# Main1.net
KiCad netlist of a schematic drawn in Altium Designer
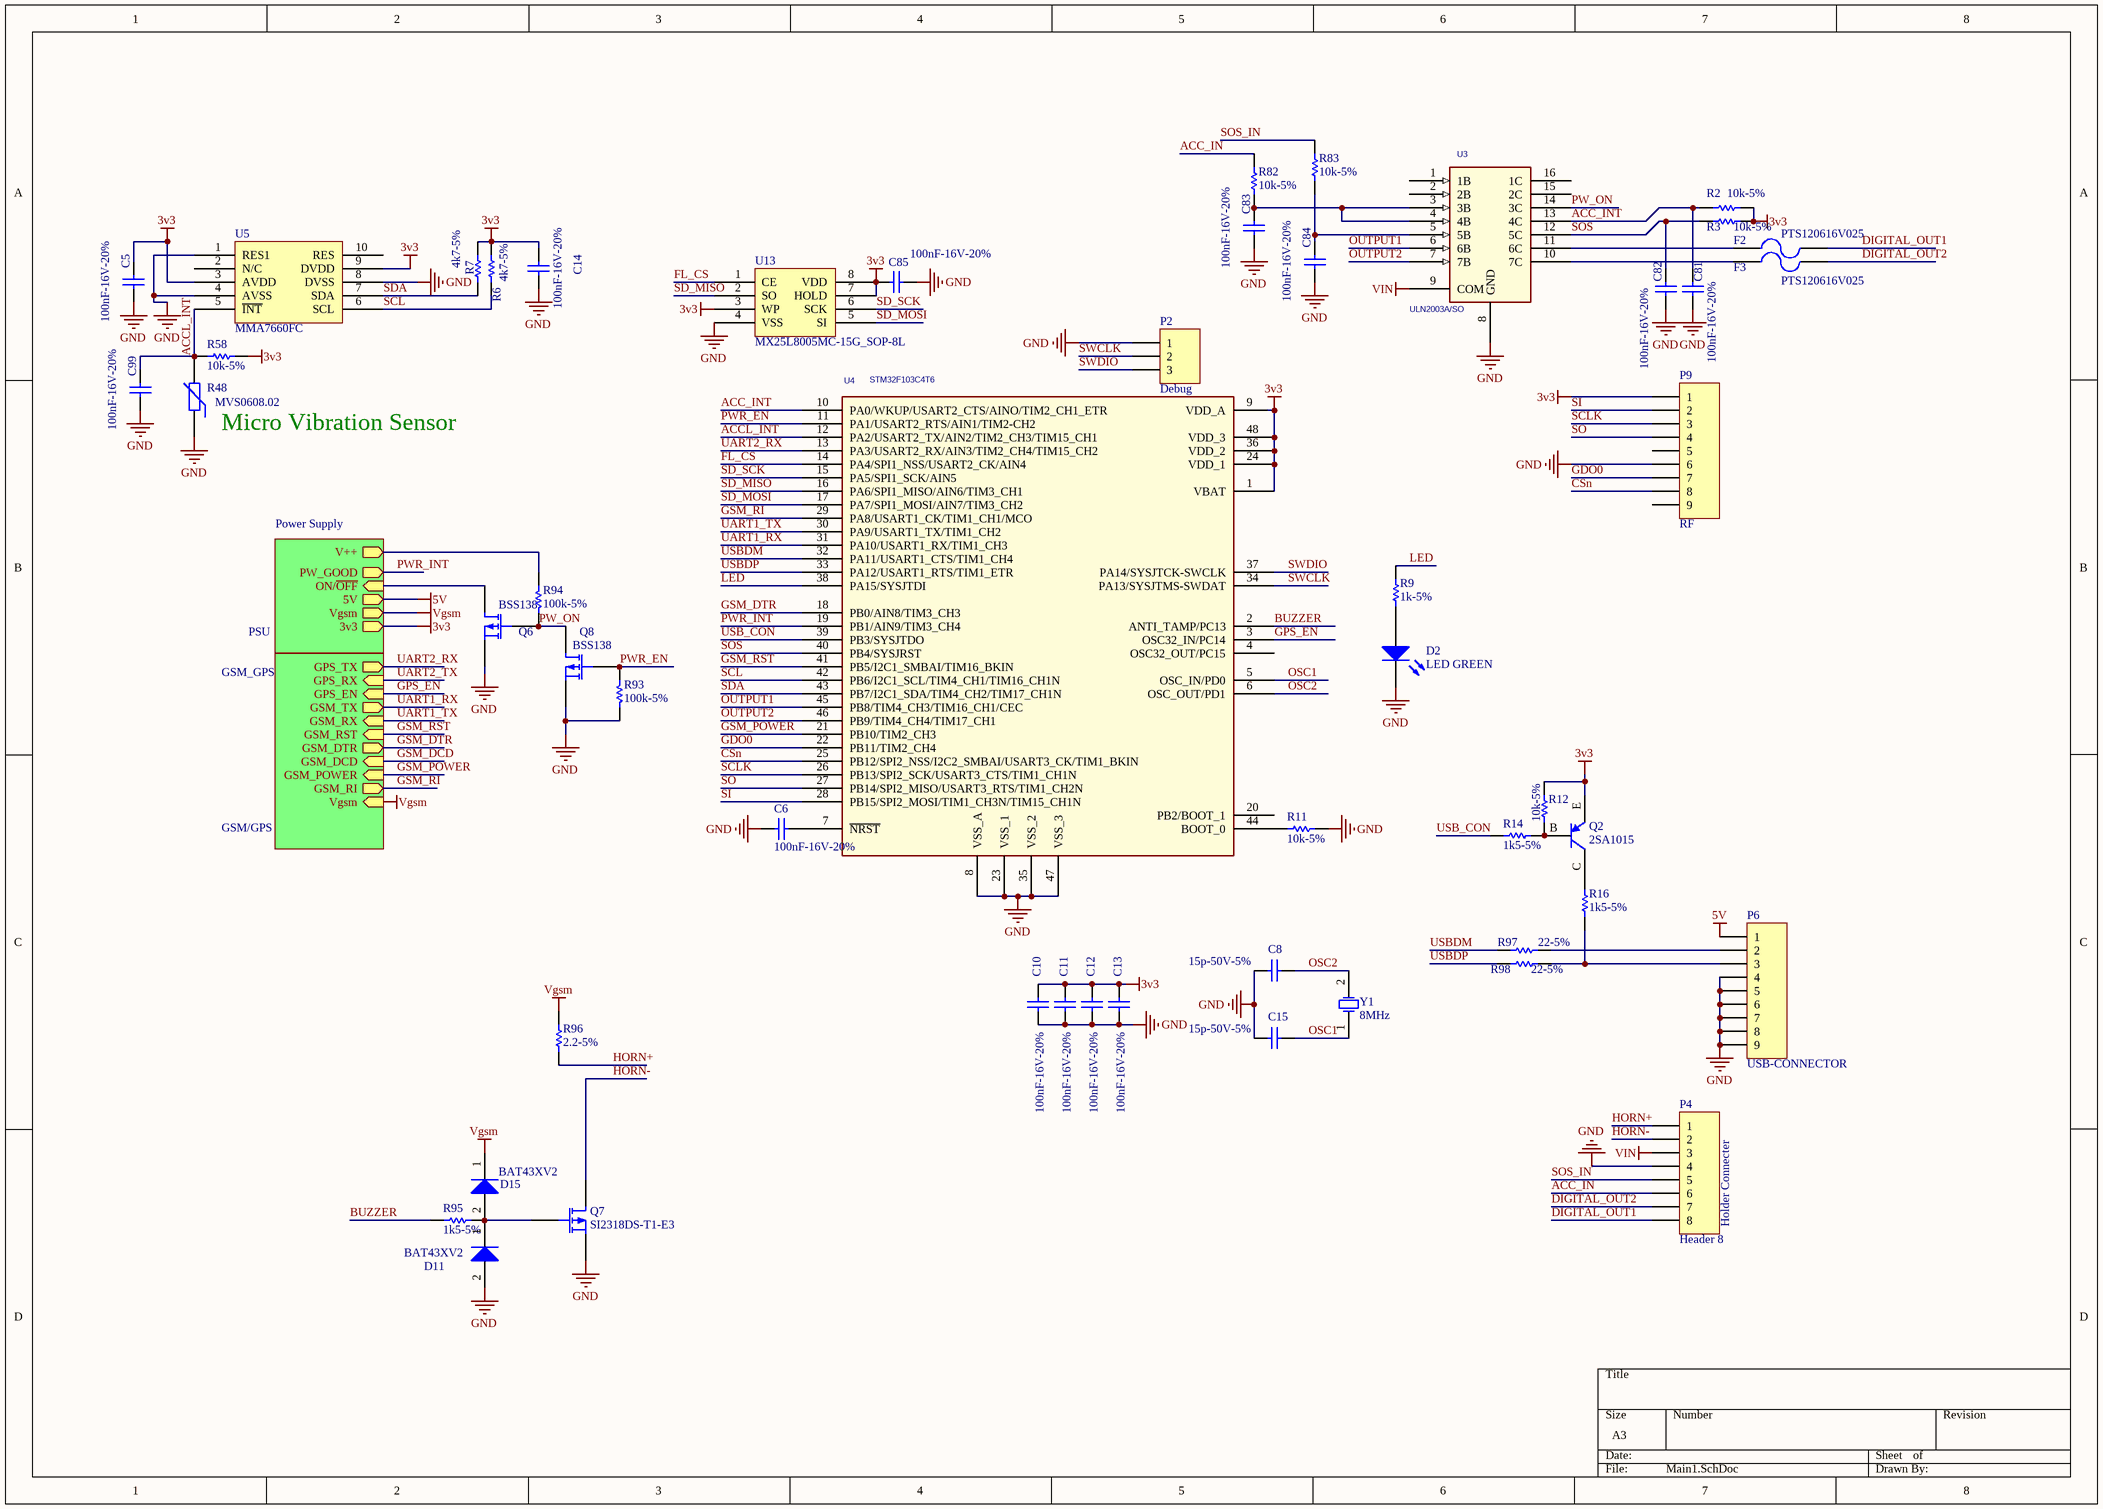
[diagram p0: Main1.SchDoc]

(export (version "E")
  (design (tool "Eeschema 10.0.6"))
  (components
    (comp (ref "C5")
      (value "100nF-16V-20%")
      (footprint "C0402")
      (description "CAP CER 0.1UF 16V Y5V 0402")
      (fields
        (field (name "MANUFACTURER") "Yageo")
        (field (name "DIGI-KEY PART NUMBER") "311-1047-1-ND")
        (field (name "PUBLISHER") "Altium Limited")
      )
      (libsource (lib "Miscellaneous Devices") (part "Cap"))
    )
    (comp (ref "C6")
      (value "100nF-16V-20%")
      (footprint "C0402")
      (description "CAP CER 0.1UF 16V Y5V 0402")
      (fields
        (field (name "MANUFACTURER") "Yageo")
        (field (name "DIGI-KEY PART NUMBER") "311-1047-1-ND")
        (field (name "PUBLISHER") "Altium Limited")
      )
      (libsource (lib "Miscellaneous Devices") (part "Cap"))
    )
    (comp (ref "C8")
      (value "15p-50V-5%")
      (footprint "C0402")
      (description "CAP CER 15PF 50V 5% NPO 0402")
      (fields
        (field (name "MANUFACTURER") "Yageo")
        (field (name "DIGI-KEY PART NUMBER") "311-1017-1-ND")
        (field (name "PUBLISHER") "Altium Limited")
      )
      (libsource (lib "Miscellaneous Devices") (part "Cap"))
    )
    (comp (ref "C10")
      (value "100nF-16V-20%")
      (footprint "C0402")
      (description "CAP CER 0.1UF 16V Y5V 0402")
      (fields
        (field (name "MANUFACTURER") "Yageo")
        (field (name "DIGI-KEY PART NUMBER") "311-1047-1-ND")
        (field (name "PUBLISHER") "Altium Limited")
      )
      (libsource (lib "Miscellaneous Devices") (part "Cap"))
    )
    (comp (ref "C11")
      (value "100nF-16V-20%")
      (footprint "C0402")
      (description "CAP CER 0.1UF 16V Y5V 0402")
      (fields
        (field (name "MANUFACTURER") "Yageo")
        (field (name "DIGI-KEY PART NUMBER") "311-1047-1-ND")
        (field (name "PUBLISHER") "Altium Limited")
      )
      (libsource (lib "Miscellaneous Devices") (part "Cap"))
    )
    (comp (ref "C12")
      (value "100nF-16V-20%")
      (footprint "C0402")
      (description "CAP CER 0.1UF 16V Y5V 0402")
      (fields
        (field (name "MANUFACTURER") "Yageo")
        (field (name "DIGI-KEY PART NUMBER") "311-1047-1-ND")
        (field (name "PUBLISHER") "Altium Limited")
      )
      (libsource (lib "Miscellaneous Devices") (part "Cap"))
    )
    (comp (ref "C13")
      (value "100nF-16V-20%")
      (footprint "C0402")
      (description "CAP CER 0.1UF 16V Y5V 0402")
      (fields
        (field (name "MANUFACTURER") "Yageo")
        (field (name "DIGI-KEY PART NUMBER") "311-1047-1-ND")
        (field (name "PUBLISHER") "Altium Limited")
      )
      (libsource (lib "Miscellaneous Devices") (part "Cap"))
    )
    (comp (ref "C14")
      (value "100nF-16V-20%")
      (footprint "C0402")
      (description "CAP CER 0.1UF 16V Y5V 0402")
      (fields
        (field (name "MANUFACTURER") "Yageo")
        (field (name "DIGI-KEY PART NUMBER") "311-1047-1-ND")
        (field (name "PUBLISHER") "Altium Limited")
      )
      (libsource (lib "Miscellaneous Devices") (part "Cap"))
    )
    (comp (ref "C15")
      (value "15p-50V-5%")
      (footprint "C0402")
      (description "CAP CER 15PF 50V 5% NPO 0402")
      (fields
        (field (name "MANUFACTURER") "Yageo")
        (field (name "DIGI-KEY PART NUMBER") "311-1017-1-ND")
        (field (name "PUBLISHER") "Altium Limited")
      )
      (libsource (lib "Miscellaneous Devices") (part "Cap"))
    )
    (comp (ref "C81")
      (value "100nF-16V-20%")
      (footprint "C0402")
      (description "CAP CER 0.1UF 16V Y5V 0402")
      (fields
        (field (name "MANUFACTURER") "Yageo")
        (field (name "DIGI-KEY PART NUMBER") "311-1047-1-ND")
        (field (name "PUBLISHER") "Altium Limited")
      )
      (libsource (lib "Miscellaneous Devices") (part "Cap"))
    )
    (comp (ref "C82")
      (value "100nF-16V-20%")
      (footprint "C0402")
      (description "CAP CER 0.1UF 16V Y5V 0402")
      (fields
        (field (name "MANUFACTURER") "Yageo")
        (field (name "DIGI-KEY PART NUMBER") "311-1047-1-ND")
        (field (name "PUBLISHER") "Altium Limited")
      )
      (libsource (lib "Miscellaneous Devices") (part "Cap"))
    )
    (comp (ref "C83")
      (value "100nF-16V-20%")
      (footprint "C0402")
      (description "CAP CER 0.1UF 16V Y5V 0402")
      (fields
        (field (name "MANUFACTURER") "Yageo")
        (field (name "DIGI-KEY PART NUMBER") "311-1047-1-ND")
        (field (name "PUBLISHER") "Altium Limited")
      )
      (libsource (lib "Miscellaneous Devices") (part "Cap"))
    )
    (comp (ref "C84")
      (value "100nF-16V-20%")
      (footprint "C0402")
      (description "CAP CER 0.1UF 16V Y5V 0402")
      (fields
        (field (name "MANUFACTURER") "Yageo")
        (field (name "DIGI-KEY PART NUMBER") "311-1047-1-ND")
        (field (name "PUBLISHER") "Altium Limited")
      )
      (libsource (lib "Miscellaneous Devices") (part "Cap"))
    )
    (comp (ref "C85")
      (value "100nF-16V-20%")
      (footprint "C0402")
      (description "CAP CER 0.1UF 16V Y5V 0402")
      (fields
        (field (name "MANUFACTURER") "Yageo")
        (field (name "DIGI-KEY PART NUMBER") "311-1047-1-ND")
        (field (name "PUBLISHER") "Altium Limited")
      )
      (libsource (lib "Miscellaneous Devices") (part "Cap"))
    )
    (comp (ref "C99")
      (value "100nF-16V-20%")
      (footprint "C0402")
      (description "CAP CER 0.1UF 16V Y5V 0402")
      (fields
        (field (name "MANUFACTURER") "Yageo")
        (field (name "DIGI-KEY PART NUMBER") "311-1047-1-ND")
        (field (name "PUBLISHER") "Altium Limited")
      )
      (libsource (lib "Miscellaneous Devices") (part "Cap"))
    )
    (comp (ref "D2")
      (value "LED GREEN")
      (footprint "LED0603-G")
      (description "LED GREEN CLEAR THIN 0603 SMD")
      (fields
        (field (name "DIGI-KEY PART NUMBER") "160-1446-2-ND")
        (field (name "MANUFACTURER") "Lite-On Inc")
        (field (name "PUBLISHER") "Altium Limited")
      )
      (libsource (lib "Miscellaneous Devices") (part "LED2"))
    )
    (comp (ref "D11")
      (value "BAT43XV2")
      (footprint "BAT43XV2")
      (description "Diode Type SMD")
      (fields
        (field (name "DIGI-KEY PART NUMBER") "BAT43XV2CT-ND")
        (field (name "MANUFACTURER") "Fairchild Semiconductor")
        (field (name "PUBLISHER") "Altium Limited")
      )
      (libsource (lib "Miscellaneous Devices") (part "Diode"))
    )
    (comp (ref "D15")
      (value "BAT43XV2")
      (footprint "BAT43XV2")
      (description "Diode Type SMD")
      (fields
        (field (name "DIGI-KEY PART NUMBER") "BAT43XV2CT-ND")
        (field (name "MANUFACTURER") "Fairchild Semiconductor")
        (field (name "PUBLISHER") "Altium Limited")
      )
      (libsource (lib "Miscellaneous Devices") (part "Diode"))
    )
    (comp (ref "F2")
      (value "PTS120616V025")
      (footprint "PTC1206")
      (description "PTC RESETTABLE SMD 1206 16V .25A")
      (fields
        (field (name "DIGI-KEY PART NUMBER") "283-3137-2-ND")
        (field (name "MANUFACTURER") "Cooper Bussmann")
        (field (name "PUBLISHER") "Altium Limited")
      )
      (libsource (lib "Miscellaneous Devices") (part "Fuse 2"))
    )
    (comp (ref "F3")
      (value "PTS120616V025")
      (footprint "PTC1206")
      (description "PTC RESETTABLE SMD 1206 16V .25A")
      (fields
        (field (name "DIGI-KEY PART NUMBER") "283-3137-2-ND")
        (field (name "MANUFACTURER") "Cooper Bussmann")
        (field (name "PUBLISHER") "Altium Limited")
      )
      (libsource (lib "Miscellaneous Devices") (part "Fuse 2"))
    )
    (comp (ref "P2")
      (value "Debug")
      (footprint "HDR1X3")
      (description "Header, 3-Pin")
      (fields (field (name "PUBLISHER") "Altium Limited"))
      (libsource (lib "Miscellaneous Connectors") (part "Header 3"))
    )
    (comp (ref "P4")
      (value "Header 8")
      (footprint "HDR1X8")
      (description "Header, 8-Pin")
      (fields (field (name "PUBLISHER") "Altium Limited"))
      (libsource (lib "Miscellaneous Connectors") (part "Header 8"))
    )
    (comp (ref "P6")
      (value "USB-CONNECTOR")
      (footprint "USB MINI B RECEPTACLE-M")
      (description "CONN RCPT USB MINI B R/A SMD")
      (fields
        (field (name "DIGI-KEY PART NUMBER") "H11671TR-ND")
        (field (name "MANUFACTURER") "Hirose Electric Co Ltd")
        (field (name "PUBLISHER") "Altium Limited")
      )
      (libsource (lib "Miscellaneous Connectors") (part "Header 9"))
    )
    (comp (ref "P9")
      (value "RF")
      (footprint "CC2500")
      (description "Header, 9-Pin")
      (fields (field (name "PUBLISHER") "Altium Limited"))
      (libsource (lib "Miscellaneous Connectors") (part "MHDR1X9"))
    )
    (comp (ref "Q2")
      (value "2SA1015")
      (footprint "SC-43-BCE")
      (fields
        (field (name "MANUFACTURER") "Toshiba")
        (field (name "MANUFACTURER PART NUMBER") "2SA1015LT1-BA")
      )
      (libsource (lib "Transistor") (part "PNP Transistor"))
    )
    (comp (ref "Q6")
      (value "BSS138")
      (footprint "SOT23-3")
      (description "MOSFET P-CH 50V 130MA SOT23-3")
      (fields
        (field (name "DIGI-KEY PART NUMBER") "BSS84-FDITR-ND")
        (field (name "MANUFACTURER") "Diodes Inc")
        (field (name "PUBLISHER") "Altium Limited")
      )
      (libsource (lib "Miscellaneous Devices") (part "MOSFET-P"))
    )
    (comp (ref "Q7")
      (value "SI2318DS-T1-E3")
      (footprint "SOT23-3")
      (description "MOSFET N-CH 40V 3A SOT23-3")
      (fields
        (field (name "DIGI-KEY PART NUMBER") "SI2318DS-T1-E3TR-ND")
        (field (name "MANUFACTURER") "Vishay Siliconix")
        (field (name "PUBLISHER") "Altium Limited")
      )
      (libsource (lib "Miscellaneous Devices") (part "MOSFET-P"))
    )
    (comp (ref "Q8")
      (value "BSS138")
      (footprint "SOT23-3")
      (description "MOSFET P-CH 50V 130MA SOT23-3")
      (fields
        (field (name "DIGI-KEY PART NUMBER") "BSS84-FDITR-ND")
        (field (name "MANUFACTURER") "Diodes Inc")
        (field (name "PUBLISHER") "Altium Limited")
      )
      (libsource (lib "Miscellaneous Devices") (part "MOSFET-P"))
    )
    (comp (ref "R2")
      (value "10k-5%")
      (footprint "R0402")
      (description "RES 10K OHM 1/16W 5% 0402 SMD")
      (fields
        (field (name "DIGI-KEY PART NUMBER") "311-10KJRCT-ND")
        (field (name "MANUFACTURER") "Yageo")
        (field (name "PUBLISHER") "Altium Limited")
      )
      (libsource (lib "Miscellaneous Devices") (part "Res1"))
    )
    (comp (ref "R3")
      (value "10k-5%")
      (footprint "R0402")
      (description "RES 10K OHM 1/16W 5% 0402 SMD")
      (fields
        (field (name "DIGI-KEY PART NUMBER") "311-10KJRCT-ND")
        (field (name "MANUFACTURER") "Yageo")
        (field (name "PUBLISHER") "Altium Limited")
      )
      (libsource (lib "Miscellaneous Devices") (part "Res1"))
    )
    (comp (ref "R6")
      (value "4k7-5%")
      (footprint "R0402")
      (description "RES 4.7K OHM 1/16W 5% 0402 SMD")
      (fields
        (field (name "DIGI-KEY PART NUMBER") "311-4.7KJRCT-ND")
        (field (name "MANUFACTURER") "Yageo")
        (field (name "PUBLISHER") "Altium Limited")
      )
      (libsource (lib "Miscellaneous Devices") (part "Res1"))
    )
    (comp (ref "R7")
      (value "4k7-5%")
      (footprint "R0402")
      (description "RES 4.7K OHM 1/16W 5% 0402 SMD")
      (fields
        (field (name "DIGI-KEY PART NUMBER") "311-4.7KJRCT-ND")
        (field (name "MANUFACTURER") "Yageo")
        (field (name "PUBLISHER") "Altium Limited")
      )
      (libsource (lib "Miscellaneous Devices") (part "Res1"))
    )
    (comp (ref "R9")
      (value "1k-5%")
      (footprint "R0402")
      (description "RES 1.0K OHM 1/16W 5% 0402 SMD")
      (fields
        (field (name "DIGI-KEY PART NUMBER") "311-1.0KJRCT-ND")
        (field (name "MANUFACTURER") "Yageo")
        (field (name "PUBLISHER") "Altium Limited")
      )
      (libsource (lib "Miscellaneous Devices") (part "Res1"))
    )
    (comp (ref "R11")
      (value "10k-5%")
      (footprint "R0402")
      (description "RES 10K OHM 1/16W 5% 0402 SMD")
      (fields
        (field (name "DIGI-KEY PART NUMBER") "311-10KJRCT-ND")
        (field (name "MANUFACTURER") "Yageo")
        (field (name "PUBLISHER") "Altium Limited")
      )
      (libsource (lib "Miscellaneous Devices") (part "Res1"))
    )
    (comp (ref "R12")
      (value "10k-5%")
      (footprint "R0402")
      (description "RES 10K OHM 1/16W 5% 0402 SMD")
      (fields
        (field (name "DIGI-KEY PART NUMBER") "311-10KJRCT-ND")
        (field (name "MANUFACTURER") "Yageo")
        (field (name "PUBLISHER") "Altium Limited")
      )
      (libsource (lib "Miscellaneous Devices") (part "Res1"))
    )
    (comp (ref "R14")
      (value "1k5-5%")
      (footprint "R0402")
      (description "RES 1.5K OHM 1/16W 5% 0402 SMD")
      (fields
        (field (name "DIGI-KEY PART NUMBER") "311-1.5KJRCT-ND")
        (field (name "MANUFACTURER") "Yageo")
        (field (name "PUBLISHER") "Altium Limited")
      )
      (libsource (lib "Miscellaneous Devices") (part "Res1"))
    )
    (comp (ref "R16")
      (value "1k5-5%")
      (footprint "R0402")
      (description "RES 1.5K OHM 1/16W 5% 0402 SMD")
      (fields
        (field (name "DIGI-KEY PART NUMBER") "311-1.5KJRCT-ND")
        (field (name "MANUFACTURER") "Yageo")
        (field (name "PUBLISHER") "Altium Limited")
      )
      (libsource (lib "Miscellaneous Devices") (part "Res1"))
    )
    (comp (ref "R48")
      (value "MVS0608.02")
      (footprint "R1210")
      (description "Micro Vibration Sensor")
      (fields (field (name "MANUFACTURER") "Tyrone") (field (name "PUBLISHER") "Altium Limited"))
      (libsource (lib "Miscellaneous Devices") (part "Res Varistor"))
    )
    (comp (ref "R58")
      (value "10k-5%")
      (footprint "R0402")
      (description "RES 10K OHM 1/16W 5% 0402 SMD")
      (fields
        (field (name "DIGI-KEY PART NUMBER") "311-10KJRCT-ND")
        (field (name "MANUFACTURER") "Yageo")
        (field (name "PUBLISHER") "Altium Limited")
      )
      (libsource (lib "Miscellaneous Devices") (part "Res1"))
    )
    (comp (ref "R82")
      (value "10k-5%")
      (footprint "R0402")
      (description "RES 10K OHM 1/16W 5% 0402 SMD")
      (fields
        (field (name "DIGI-KEY PART NUMBER") "311-10KJRCT-ND")
        (field (name "MANUFACTURER") "Yageo")
        (field (name "PUBLISHER") "Altium Limited")
      )
      (libsource (lib "Miscellaneous Devices") (part "Res1"))
    )
    (comp (ref "R83")
      (value "10k-5%")
      (footprint "R0402")
      (description "RES 10K OHM 1/16W 5% 0402 SMD")
      (fields
        (field (name "DIGI-KEY PART NUMBER") "311-10KJRCT-ND")
        (field (name "MANUFACTURER") "Yageo")
        (field (name "PUBLISHER") "Altium Limited")
      )
      (libsource (lib "Miscellaneous Devices") (part "Res1"))
    )
    (comp (ref "R93")
      (value "100k-5%")
      (footprint "R0402")
      (description "RES 100K OHM 1/16W 5% 0402 SMD")
      (fields
        (field (name "DIGI-KEY PART NUMBER") "311-100KJRCT-ND")
        (field (name "MANUFACTURER") "Yageo")
        (field (name "PUBLISHER") "Altium Limited")
      )
      (libsource (lib "Miscellaneous Devices") (part "Res1"))
    )
    (comp (ref "R94")
      (value "100k-5%")
      (footprint "R0402")
      (description "RES 100K OHM 1/16W 5% 0402 SMD")
      (fields
        (field (name "DIGI-KEY PART NUMBER") "311-100KJRCT-ND")
        (field (name "MANUFACTURER") "Yageo")
        (field (name "PUBLISHER") "Altium Limited")
      )
      (libsource (lib "Miscellaneous Devices") (part "Res1"))
    )
    (comp (ref "R95")
      (value "1k5-5%")
      (footprint "R0402")
      (description "RES 1.5K OHM 1/16W 5% 0402 SMD")
      (fields
        (field (name "DIGI-KEY PART NUMBER") "311-1.5KJRCT-ND")
        (field (name "MANUFACTURER") "Yageo")
        (field (name "PUBLISHER") "Altium Limited")
      )
      (libsource (lib "Miscellaneous Devices") (part "Res1"))
    )
    (comp (ref "R96")
      (value "2.2-5%")
      (footprint "R0805")
      (description "RES 2.2 OHM 1/16W 5% 0402 SMD")
      (fields
        (field (name "DIGI-KEY PART NUMBER") "311-2.2JRCT-ND")
        (field (name "MANUFACTURER") "Yageo")
        (field (name "PUBLISHER") "Altium Limited")
      )
      (libsource (lib "Miscellaneous Devices") (part "Res1"))
    )
    (comp (ref "R97")
      (value "22-5%")
      (footprint "R0402")
      (description "RES 22 OHM 1/16W 5% 0402 SMD")
      (fields
        (field (name "DIGI-KEY PART NUMBER") "311-22JRCT-ND")
        (field (name "MANUFACTURER") "Yageo")
        (field (name "PUBLISHER") "Altium Limited")
      )
      (libsource (lib "Miscellaneous Devices") (part "Res1"))
    )
    (comp (ref "R98")
      (value "22-5%")
      (footprint "R0402")
      (description "RES 22 OHM 1/16W 5% 0402 SMD")
      (fields
        (field (name "DIGI-KEY PART NUMBER") "311-22JRCT-ND")
        (field (name "MANUFACTURER") "Yageo")
        (field (name "PUBLISHER") "Altium Limited")
      )
      (libsource (lib "Miscellaneous Devices") (part "Res1"))
    )
    (comp (ref "U3")
      (value "ULN2003A/SO")
      (footprint "SO16-150mil")
      (description "IC DARL TRANS ARRAY 16-SOIC")
      (fields
        (field (name "DIGI-KEY PART NUMBER") "296-1368-2-ND")
        (field (name "MANUFACTURER PART NUMBER") "ULN2003ADR")
      )
      (libsource (lib "*") (part "ULN2003A/SO_0"))
    )
    (comp (ref "U4")
      (value "STM32F103C4T6")
      (footprint "TQFP-48-P0.5")
      (description "MCU ARM 64KB FLASH MEM 48-LQFP")
      (fields
        (field (name "DIGI-KEY PART NUMBER") "497-6063-ND")
        (field (name "MANUFACTURER") "STMicroelectronics")
      )
      (libsource (lib "*") (part "ATmega128_4"))
    )
    (comp (ref "U5")
      (value "MMA7660FC")
      (footprint "MMA7660FC")
      (description "ACCELEROMETER 3X3 DGTL 10-DFN")
      (fields
        (field (name "DIGI-KEY PART NUMBER") "MMA7660FCT-ND")
        (field (name "MANUFACTURER") "Freescale Semiconductor")
      )
      (libsource (lib "Lib") (part "MMA7660FC"))
    )
    (comp (ref "U13")
      (value "MX25L8005MC-15G_SOP-8L")
      (footprint "SO8-150mil")
      (fields (field (name "MANUFACTURER") "Tyrone"))
      (libsource (lib "My LB") (part "FlashIC"))
    )
    (comp (ref "Y1")
      (value "8MHz")
      (footprint "HC49/US-SMD")
      (description "CRYSTAL 8.000MHZ 18PF SMD")
      (fields
        (field (name "DIGI-KEY PART NUMBER") "535-9089-1-ND")
        (field (name "MANUFACTURER") "Abracon Corporation")
        (field (name "PUBLISHER") "Altium Limited")
      )
      (libsource (lib "Miscellaneous Devices") (part "XTAL"))
    )
  )
  (nets
    (net (code "1") (name "/ACCL_INT") (class "Default")
      (node (ref "C99") (pin "2") (pinfunction "2_2") (pintype "passive"))
      (node (ref "R48") (pin "2") (pinfunction "2_2") (pintype "passive"))
      (node (ref "R58") (pin "1") (pinfunction "1_1") (pintype "passive"))
      (node (ref "U4") (pin "12") (pinfunction "PA2/USART2_TX/AIN2/TIM2_CH3/TIM15_CH1_12") (pintype "passive"))
      (node (ref "U5") (pin "5") (pinfunction "~{INT}_5") (pintype "passive"))
    )
    (net (code "2") (name "/ACC_IN") (class "Default")
      (node (ref "P4") (pin "6") (pinfunction "6_6") (pintype "passive"))
      (node (ref "R82") (pin "2") (pinfunction "2_2") (pintype "passive"))
    )
    (net (code "3") (name "/ACC_INT") (class "Default")
      (node (ref "C81") (pin "2") (pinfunction "2_2") (pintype "passive"))
      (node (ref "R2") (pin "1") (pinfunction "1_1") (pintype "passive"))
      (node (ref "U3") (pin "13") (pinfunction "4C_13") (pintype "open_collector"))
      (node (ref "U4") (pin "10") (pinfunction "PA0/WKUP/USART2_CTS/AINO/TIM2_CH1_ETR_10") (pintype "passive"))
    )
    (net (code "4") (name "/BUZZER") (class "Default")
      (node (ref "R95") (pin "2") (pinfunction "2_2") (pintype "passive"))
      (node (ref "U4") (pin "2") (pinfunction "ANTI_TAMP/PC13_2") (pintype "passive"))
    )
    (net (code "5") (name "/CSn") (class "Default")
      (node (ref "P9") (pin "8") (pinfunction "8_8") (pintype "passive"))
      (node (ref "U4") (pin "25") (pinfunction "PB12/SPI2_NSS/I2C2_SMBAI/USART3_CK/TIM1_BKIN_25") (pintype "passive"))
    )
    (net (code "6") (name "/DIGITAL_OUT1") (class "Default")
      (node (ref "F2") (pin "1") (pinfunction "1_1") (pintype "passive"))
      (node (ref "P4") (pin "8") (pinfunction "8_8") (pintype "passive"))
    )
    (net (code "7") (name "/DIGITAL_OUT2") (class "Default")
      (node (ref "F3") (pin "1") (pinfunction "1_1") (pintype "passive"))
      (node (ref "P4") (pin "7") (pinfunction "7_7") (pintype "passive"))
    )
    (net (code "8") (name "/FL_CS") (class "Default")
      (node (ref "U13") (pin "1") (pinfunction "CE_1") (pintype "passive"))
      (node (ref "U4") (pin "14") (pinfunction "PA4/SPI1_NSS/USART2_CK/AIN4_14") (pintype "passive"))
    )
    (net (code "9") (name "/GDO0") (class "Default")
      (node (ref "P9") (pin "7") (pinfunction "7_7") (pintype "passive"))
      (node (ref "U4") (pin "22") (pinfunction "PB11/TIM2_CH4_22") (pintype "passive"))
    )
    (net (code "10") (name "/GPS_EN") (class "Default")
      (node (ref "U4") (pin "3") (pinfunction "OSC32_IN/PC14_3") (pintype "passive"))
    )
    (net (code "12") (name "/GSM_DTR") (class "Default")
      (node (ref "U4") (pin "18") (pinfunction "PB0/AIN8/TIM3_CH3_18") (pintype "passive"))
    )
    (net (code "13") (name "/GSM_POWER") (class "Default")
      (node (ref "U4") (pin "21") (pinfunction "PB10/TIM2_CH3_21") (pintype "passive"))
    )
    (net (code "14") (name "/GSM_RI") (class "Default")
      (node (ref "U4") (pin "29") (pinfunction "PA8/USART1_CK/TIM1_CH1/MCO_29") (pintype "passive"))
    )
    (net (code "15") (name "/GSM_RST") (class "Default")
      (node (ref "U4") (pin "41") (pinfunction "PB5/I2C1_SMBAI/TIM16_BKIN_41") (pintype "passive"))
    )
    (net (code "16") (name "/HORN+") (class "Default")
      (node (ref "P4") (pin "1") (pinfunction "1_1") (pintype "passive"))
      (node (ref "R96") (pin "2") (pinfunction "2_2") (pintype "passive"))
    )
    (net (code "17") (name "/HORN-") (class "Default")
      (node (ref "P4") (pin "2") (pinfunction "2_2") (pintype "passive"))
      (node (ref "Q7") (pin "3") (pinfunction "D_3") (pintype "passive"))
    )
    (net (code "18") (name "/LED") (class "Default")
      (node (ref "R9") (pin "2") (pinfunction "2_2") (pintype "passive"))
      (node (ref "U4") (pin "38") (pinfunction "PA15/SYSJTDI_38") (pintype "passive"))
    )
    (net (code "19") (name "/ON{slash}~{OFF}") (class "Default")
      (node (ref "Q6") (pin "3") (pinfunction "D_3") (pintype "passive"))
    )
    (net (code "20") (name "/OSC1") (class "Default")
      (node (ref "C15") (pin "2") (pinfunction "2_2") (pintype "passive"))
      (node (ref "U4") (pin "5") (pinfunction "OSC_IN/PD0_5") (pintype "passive"))
      (node (ref "Y1") (pin "1") (pinfunction "OSC1_1") (pintype "passive"))
    )
    (net (code "21") (name "/OSC2") (class "Default")
      (node (ref "C8") (pin "2") (pinfunction "2_2") (pintype "passive"))
      (node (ref "U4") (pin "6") (pinfunction "OSC_OUT/PD1_6") (pintype "passive"))
      (node (ref "Y1") (pin "2") (pinfunction "OSC2_2") (pintype "passive"))
    )
    (net (code "22") (name "/OUTPUT1") (class "Default")
      (node (ref "U3") (pin "6") (pinfunction "6B_6") (pintype "input"))
      (node (ref "U4") (pin "45") (pinfunction "PB8/TIM4_CH3/TIM16_CH1/CEC_45") (pintype "passive"))
    )
    (net (code "23") (name "/OUTPUT2") (class "Default")
      (node (ref "U3") (pin "7") (pinfunction "7B_7") (pintype "input"))
      (node (ref "U4") (pin "46") (pinfunction "PB9/TIM4_CH4/TIM17_CH1_46") (pintype "passive"))
    )
    (net (code "24") (name "/PWR_EN") (class "Default")
      (node (ref "Q8") (pin "1") (pinfunction "G_1") (pintype "passive"))
      (node (ref "R93") (pin "1") (pinfunction "1_1") (pintype "passive"))
      (node (ref "U4") (pin "11") (pinfunction "PA1/USART2_RTS/AIN1/TIM2-CH2_11") (pintype "passive"))
    )
    (net (code "25") (name "/PWR_INT") (class "Default")
      (node (ref "U4") (pin "19") (pinfunction "PB1/AIN9/TIM3_CH4_19") (pintype "passive"))
    )
    (net (code "26") (name "/PW_ON") (class "Default")
      (node (ref "Q6") (pin "1") (pinfunction "G_1") (pintype "passive"))
      (node (ref "Q8") (pin "3") (pinfunction "D_3") (pintype "passive"))
      (node (ref "R94") (pin "2") (pinfunction "2_2") (pintype "passive"))
      (node (ref "U3") (pin "14") (pinfunction "3C_14") (pintype "open_collector"))
    )
    (net (code "27") (name "/SCL") (class "Default")
      (node (ref "R6") (pin "1") (pinfunction "1_1") (pintype "passive"))
      (node (ref "U4") (pin "42") (pinfunction "PB6/I2C1_SCL/TIM4_CH1/TIM16_CH1N_42") (pintype "passive"))
      (node (ref "U5") (pin "6") (pinfunction "SCL_6") (pintype "passive"))
    )
    (net (code "28") (name "/SCLK") (class "Default")
      (node (ref "P9") (pin "3") (pinfunction "3_3") (pintype "passive"))
      (node (ref "U4") (pin "26") (pinfunction "PB13/SPI2_SCK/USART3_CTS/TIM1_CH1N_26") (pintype "passive"))
    )
    (net (code "29") (name "/SDA") (class "Default")
      (node (ref "R7") (pin "1") (pinfunction "1_1") (pintype "passive"))
      (node (ref "U4") (pin "43") (pinfunction "PB7/I2C1_SDA/TIM4_CH2/TIM17_CH1N_43") (pintype "passive"))
      (node (ref "U5") (pin "7") (pinfunction "SDA_7") (pintype "passive"))
    )
    (net (code "30") (name "/SD_MISO") (class "Default")
      (node (ref "U13") (pin "2") (pinfunction "SO_2") (pintype "passive"))
      (node (ref "U4") (pin "16") (pinfunction "PA6/SPI1_MISO/AIN6/TIM3_CH1_16") (pintype "passive"))
    )
    (net (code "31") (name "/SD_MOSI") (class "Default")
      (node (ref "U13") (pin "5") (pinfunction "SI_5") (pintype "passive"))
      (node (ref "U4") (pin "17") (pinfunction "PA7/SPI1_MOSI/AIN7/TIM3_CH2_17") (pintype "passive"))
    )
    (net (code "32") (name "/SD_SCK") (class "Default")
      (node (ref "U13") (pin "6") (pinfunction "SCK_6") (pintype "passive"))
      (node (ref "U4") (pin "15") (pinfunction "PA5/SPI1_SCK/AIN5_15") (pintype "passive"))
    )
    (net (code "33") (name "/SI") (class "Default")
      (node (ref "P9") (pin "2") (pinfunction "2_2") (pintype "passive"))
      (node (ref "U4") (pin "28") (pinfunction "PB15/SPI2_MOSI/TIM1_CH3N/TIM15_CH1N_28") (pintype "passive"))
    )
    (net (code "34") (name "/SO") (class "Default")
      (node (ref "P9") (pin "4") (pinfunction "4_4") (pintype "passive"))
      (node (ref "U4") (pin "27") (pinfunction "PB14/SPI2_MISO/USART3_RTS/TIM1_CH2N_27") (pintype "passive"))
    )
    (net (code "35") (name "/SOS") (class "Default")
      (node (ref "C82") (pin "2") (pinfunction "2_2") (pintype "passive"))
      (node (ref "R3") (pin "1") (pinfunction "1_1") (pintype "passive"))
      (node (ref "U3") (pin "12") (pinfunction "5C_12") (pintype "open_collector"))
      (node (ref "U4") (pin "40") (pinfunction "PB4/SYSJRST_40") (pintype "passive"))
    )
    (net (code "36") (name "/SOS_IN") (class "Default")
      (node (ref "P4") (pin "5") (pinfunction "5_5") (pintype "passive"))
      (node (ref "R83") (pin "2") (pinfunction "2_2") (pintype "passive"))
    )
    (net (code "37") (name "/SWCLK") (class "Default")
      (node (ref "P2") (pin "2") (pinfunction "2_2") (pintype "passive"))
      (node (ref "U4") (pin "34") (pinfunction "PA13/SYSJTMS-SWDAT_34") (pintype "passive"))
    )
    (net (code "38") (name "/SWDIO") (class "Default")
      (node (ref "P2") (pin "3") (pinfunction "3_3") (pintype "passive"))
      (node (ref "U4") (pin "37") (pinfunction "PA14/SYSJTCK-SWCLK_37") (pintype "passive"))
    )
    (net (code "39") (name "/UART1_RX") (class "Default")
      (node (ref "U4") (pin "31") (pinfunction "PA10/USART1_RX/TIM1_CH3_31") (pintype "passive"))
    )
    (net (code "40") (name "/UART1_TX") (class "Default")
      (node (ref "U4") (pin "30") (pinfunction "PA9/USART1_TX/TIM1_CH2_30") (pintype "passive"))
    )
    (net (code "41") (name "/UART2_RX") (class "Default")
      (node (ref "U4") (pin "13") (pinfunction "PA3/USART2_RX/AIN3/TIM2_CH4/TIM15_CH2_13") (pintype "passive"))
    )
    (net (code "43") (name "/USBDM") (class "Default")
      (node (ref "R97") (pin "1") (pinfunction "1_1") (pintype "passive"))
      (node (ref "U4") (pin "32") (pinfunction "PA11/USART1_CTS/TIM1_CH4_32") (pintype "passive"))
    )
    (net (code "44") (name "/USBDP") (class "Default")
      (node (ref "R98") (pin "1") (pinfunction "1_1") (pintype "passive"))
      (node (ref "U4") (pin "33") (pinfunction "PA12/USART1_RTS/TIM1_ETR_33") (pintype "passive"))
    )
    (net (code "45") (name "/USB_CON") (class "Default")
      (node (ref "R14") (pin "2") (pinfunction "2_2") (pintype "passive"))
      (node (ref "U4") (pin "39") (pinfunction "PB3/SYSJTDO_39") (pintype "passive"))
    )
    (net (code "46") (name "/V++") (class "Default")
      (node (ref "R94") (pin "1") (pinfunction "1_1") (pintype "passive"))
    )
    (net (code "47") (name "3v3") (class "Default")
      (node (ref "C10") (pin "1") (pinfunction "1_1") (pintype "passive"))
      (node (ref "C11") (pin "1") (pinfunction "1_1") (pintype "passive"))
      (node (ref "C12") (pin "1") (pinfunction "1_1") (pintype "passive"))
      (node (ref "C13") (pin "1") (pinfunction "1_1") (pintype "passive"))
      (node (ref "C14") (pin "2") (pinfunction "2_2") (pintype "passive"))
      (node (ref "C5") (pin "2") (pinfunction "2_2") (pintype "passive"))
      (node (ref "C85") (pin "1") (pinfunction "1_1") (pintype "passive"))
      (node (ref "P9") (pin "1") (pinfunction "1_1") (pintype "passive"))
      (node (ref "Q2") (pin "E") (pinfunction "E_E") (pintype "passive"))
      (node (ref "R12") (pin "2") (pinfunction "2_2") (pintype "passive"))
      (node (ref "R2") (pin "2") (pinfunction "2_2") (pintype "passive"))
      (node (ref "R3") (pin "2") (pinfunction "2_2") (pintype "passive"))
      (node (ref "R58") (pin "2") (pinfunction "2_2") (pintype "passive"))
      (node (ref "R6") (pin "2") (pinfunction "2_2") (pintype "passive"))
      (node (ref "R7") (pin "2") (pinfunction "2_2") (pintype "passive"))
      (node (ref "U13") (pin "3") (pinfunction "WP_3") (pintype "passive"))
      (node (ref "U13") (pin "7") (pinfunction "HOLD_7") (pintype "passive"))
      (node (ref "U13") (pin "8") (pinfunction "VDD_8") (pintype "passive"))
      (node (ref "U4") (pin "1") (pinfunction "VBAT_1") (pintype "passive"))
      (node (ref "U4") (pin "24") (pinfunction "VDD_1_24") (pintype "passive"))
      (node (ref "U4") (pin "36") (pinfunction "VDD_2_36") (pintype "passive"))
      (node (ref "U4") (pin "48") (pinfunction "VDD_3_48") (pintype "passive"))
      (node (ref "U4") (pin "9") (pinfunction "VDD_A_9") (pintype "passive"))
      (node (ref "U5") (pin "3") (pinfunction "AVDD_3") (pintype "passive"))
      (node (ref "U5") (pin "9") (pinfunction "DVDD_9") (pintype "passive"))
    )
    (net (code "48") (name "5V") (class "Default")
      (node (ref "P6") (pin "1") (pinfunction "1_1") (pintype "passive"))
    )
    (net (code "49") (name "GND") (class "Default")
      (node (ref "C10") (pin "2") (pinfunction "2_2") (pintype "passive"))
      (node (ref "C11") (pin "2") (pinfunction "2_2") (pintype "passive"))
      (node (ref "C12") (pin "2") (pinfunction "2_2") (pintype "passive"))
      (node (ref "C13") (pin "2") (pinfunction "2_2") (pintype "passive"))
      (node (ref "C14") (pin "1") (pinfunction "1_1") (pintype "passive"))
      (node (ref "C15") (pin "1") (pinfunction "1_1") (pintype "passive"))
      (node (ref "C5") (pin "1") (pinfunction "1_1") (pintype "passive"))
      (node (ref "C6") (pin "2") (pinfunction "2_2") (pintype "passive"))
      (node (ref "C8") (pin "1") (pinfunction "1_1") (pintype "passive"))
      (node (ref "C81") (pin "1") (pinfunction "1_1") (pintype "passive"))
      (node (ref "C82") (pin "1") (pinfunction "1_1") (pintype "passive"))
      (node (ref "C83") (pin "1") (pinfunction "1_1") (pintype "passive"))
      (node (ref "C84") (pin "1") (pinfunction "1_1") (pintype "passive"))
      (node (ref "C85") (pin "2") (pinfunction "2_2") (pintype "passive"))
      (node (ref "C99") (pin "1") (pinfunction "1_1") (pintype "passive"))
      (node (ref "D11") (pin "2") (pinfunction "A_2") (pintype "passive"))
      (node (ref "D2") (pin "2") (pinfunction "K_2") (pintype "passive"))
      (node (ref "P2") (pin "1") (pinfunction "1_1") (pintype "passive"))
      (node (ref "P4") (pin "4") (pinfunction "4_4") (pintype "passive"))
      (node (ref "P6") (pin "4") (pinfunction "4_4") (pintype "passive"))
      (node (ref "P6") (pin "5") (pinfunction "5_5") (pintype "passive"))
      (node (ref "P6") (pin "6") (pinfunction "6_6") (pintype "passive"))
      (node (ref "P6") (pin "7") (pinfunction "7_7") (pintype "passive"))
      (node (ref "P6") (pin "8") (pinfunction "8_8") (pintype "passive"))
      (node (ref "P6") (pin "9") (pinfunction "9_9") (pintype "passive"))
      (node (ref "P9") (pin "6") (pinfunction "6_6") (pintype "passive"))
      (node (ref "Q6") (pin "2") (pinfunction "S_2") (pintype "passive"))
      (node (ref "Q7") (pin "2") (pinfunction "S_2") (pintype "passive"))
      (node (ref "Q8") (pin "2") (pinfunction "S_2") (pintype "passive"))
      (node (ref "R11") (pin "1") (pinfunction "1_1") (pintype "passive"))
      (node (ref "R48") (pin "1") (pinfunction "1_1") (pintype "passive"))
      (node (ref "R93") (pin "2") (pinfunction "2_2") (pintype "passive"))
      (node (ref "U13") (pin "4") (pinfunction "VSS_4") (pintype "passive"))
      (node (ref "U3") (pin "8") (pinfunction "GND_8") (pintype "power_in"))
      (node (ref "U4") (pin "23") (pinfunction "VSS_1_23") (pintype "passive"))
      (node (ref "U4") (pin "35") (pinfunction "VSS_2_35") (pintype "passive"))
      (node (ref "U4") (pin "47") (pinfunction "VSS_3_47") (pintype "passive"))
      (node (ref "U4") (pin "8") (pinfunction "VSS_A_8") (pintype "passive"))
      (node (ref "U5") (pin "1") (pinfunction "RES1_1") (pintype "passive"))
      (node (ref "U5") (pin "4") (pinfunction "AVSS_4") (pintype "passive"))
      (node (ref "U5") (pin "8") (pinfunction "DVSS_8") (pintype "passive"))
    )
    (net (code "50") (name "Net-(D2-A)") (class "Default")
      (node (ref "D2") (pin "1") (pinfunction "A_1") (pintype "passive"))
      (node (ref "R9") (pin "1") (pinfunction "1_1") (pintype "passive"))
    )
    (net (code "51") (name "Net-(D11-K)") (class "Default")
      (node (ref "D11") (pin "1") (pinfunction "K_1") (pintype "passive"))
      (node (ref "D15") (pin "2") (pinfunction "A_2") (pintype "passive"))
      (node (ref "Q7") (pin "1") (pinfunction "G_1") (pintype "passive"))
      (node (ref "R95") (pin "1") (pinfunction "1_1") (pintype "passive"))
    )
    (net (code "52") (name "Net-(P6-Pad2)") (class "Default")
      (node (ref "P6") (pin "2") (pinfunction "2_2") (pintype "passive"))
      (node (ref "R97") (pin "2") (pinfunction "2_2") (pintype "passive"))
    )
    (net (code "53") (name "Net-(P6-Pad3)") (class "Default")
      (node (ref "P6") (pin "3") (pinfunction "3_3") (pintype "passive"))
      (node (ref "R16") (pin "2") (pinfunction "2_2") (pintype "passive"))
      (node (ref "R98") (pin "2") (pinfunction "2_2") (pintype "passive"))
    )
    (net (code "54") (name "Net-(Q2-PadB)") (class "Default")
      (node (ref "Q2") (pin "B") (pinfunction "B_B") (pintype "passive"))
      (node (ref "R12") (pin "1") (pinfunction "1_1") (pintype "passive"))
      (node (ref "R14") (pin "1") (pinfunction "1_1") (pintype "passive"))
    )
    (net (code "55") (name "Net-(Q2-PadC)") (class "Default")
      (node (ref "Q2") (pin "C") (pinfunction "C_C") (pintype "passive"))
      (node (ref "R16") (pin "1") (pinfunction "1_1") (pintype "passive"))
    )
    (net (code "56") (name "Net-(U3-3B)") (class "Default")
      (node (ref "C83") (pin "2") (pinfunction "2_2") (pintype "passive"))
      (node (ref "R82") (pin "1") (pinfunction "1_1") (pintype "passive"))
      (node (ref "U3") (pin "3") (pinfunction "3B_3") (pintype "input"))
      (node (ref "U3") (pin "4") (pinfunction "4B_4") (pintype "input"))
    )
    (net (code "57") (name "Net-(U3-5B)") (class "Default")
      (node (ref "C84") (pin "2") (pinfunction "2_2") (pintype "passive"))
      (node (ref "R83") (pin "1") (pinfunction "1_1") (pintype "passive"))
      (node (ref "U3") (pin "5") (pinfunction "5B_5") (pintype "input"))
    )
    (net (code "58") (name "Net-(U3-6C)") (class "Default")
      (node (ref "F2") (pin "2") (pinfunction "2_2") (pintype "passive"))
      (node (ref "U3") (pin "11") (pinfunction "6C_11") (pintype "open_collector"))
    )
    (net (code "59") (name "Net-(U3-7C)") (class "Default")
      (node (ref "F3") (pin "2") (pinfunction "2_2") (pintype "passive"))
      (node (ref "U3") (pin "10") (pinfunction "7C_10") (pintype "open_collector"))
    )
    (net (code "60") (name "Net-(U4-BOOT_0)") (class "Default")
      (node (ref "R11") (pin "2") (pinfunction "2_2") (pintype "passive"))
      (node (ref "U4") (pin "44") (pinfunction "BOOT_0_44") (pintype "passive"))
    )
    (net (code "61") (name "Net-(U4-~{NRST})") (class "Default")
      (node (ref "C6") (pin "1") (pinfunction "1_1") (pintype "passive"))
      (node (ref "U4") (pin "7") (pinfunction "~{NRST}_7") (pintype "passive"))
    )
    (net (code "62") (name "VIN") (class "Default")
      (node (ref "P4") (pin "3") (pinfunction "3_3") (pintype "passive"))
      (node (ref "U3") (pin "9") (pinfunction "COM_9") (pintype "passive"))
    )
    (net (code "63") (name "Vgsm") (class "Default")
      (node (ref "D15") (pin "1") (pinfunction "K_1") (pintype "passive"))
      (node (ref "R96") (pin "1") (pinfunction "1_1") (pintype "passive"))
    )
    (net (code "64") (name "unconnected-(P9-Pad5)") (class "Default")
      (node (ref "P9") (pin "5") (pinfunction "5_5") (pintype "passive"))
    )
    (net (code "65") (name "unconnected-(P9-Pad9)") (class "Default")
      (node (ref "P9") (pin "9") (pinfunction "9_9") (pintype "passive"))
    )
    (net (code "66") (name "unconnected-(U3-1B-Pad1)") (class "Default")
      (node (ref "U3") (pin "1") (pinfunction "1B_1") (pintype "input"))
    )
    (net (code "67") (name "unconnected-(U3-1C-Pad16)") (class "Default")
      (node (ref "U3") (pin "16") (pinfunction "1C_16") (pintype "open_collector"))
    )
    (net (code "68") (name "unconnected-(U3-2B-Pad2)") (class "Default")
      (node (ref "U3") (pin "2") (pinfunction "2B_2") (pintype "input"))
    )
    (net (code "69") (name "unconnected-(U3-2C-Pad15)") (class "Default")
      (node (ref "U3") (pin "15") (pinfunction "2C_15") (pintype "open_collector"))
    )
    (net (code "70") (name "unconnected-(U4-OSC32_OUT{slash}PC15-Pad4)") (class "Default")
      (node (ref "U4") (pin "4") (pinfunction "OSC32_OUT/PC15_4") (pintype "passive"))
    )
    (net (code "71") (name "unconnected-(U4-PB2{slash}BOOT_1-Pad20)") (class "Default")
      (node (ref "U4") (pin "20") (pinfunction "PB2/BOOT_1_20") (pintype "passive"))
    )
    (net (code "72") (name "unconnected-(U5-N{slash}C-Pad2)") (class "Default")
      (node (ref "U5") (pin "2") (pinfunction "N/C_2") (pintype "passive"))
    )
    (net (code "73") (name "unconnected-(U5-RES-Pad10)") (class "Default")
      (node (ref "U5") (pin "10") (pinfunction "RES_10") (pintype "passive"))
    )
  )
)
